# GSM_Signal_Control.net
KiCad netlist of a schematic drawn in Altium Designer
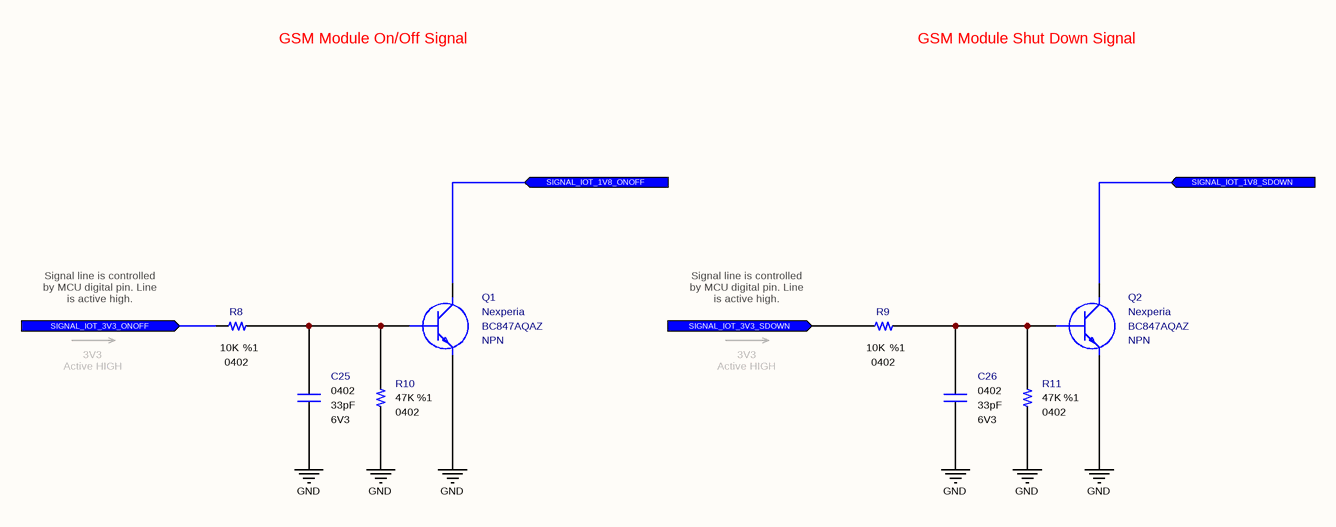
[diagram p0: GSM Signal Control.SchDoc]

(export (version "E")
  (design (tool "Eeschema 10.0.6"))
  (components
    (comp (ref "C25")
      (value "33pF")
      (footprint "CAPACITOR_0402")
      (description "Capacitor - 33pF [0402] (Ceramic)")
      (fields
        (field (name "CASE") "0402")
        (field (name "TOLERANCE") "10%")
        (field (name "VOLTAGE") "6V3")
        (field (name "MANUFACTURER PART NUMBER") "C0402C330J9RACAUTO")
      )
      (libsource (lib "Ovoo_Library") (part "Capacitor - 33pF [0402-6V3]"))
    )
    (comp (ref "C26")
      (value "33pF")
      (footprint "CAPACITOR_0402")
      (description "Capacitor - 33pF [0402] (Ceramic)")
      (fields
        (field (name "CASE") "0402")
        (field (name "TOLERANCE") "10%")
        (field (name "VOLTAGE") "6V3")
        (field (name "MANUFACTURER PART NUMBER") "C0402C330J9RACAUTO")
      )
      (libsource (lib "Ovoo_Library") (part "Capacitor - 33pF [0402-6V3]"))
    )
    (comp (ref "Q1")
      (value "Bipolar NPN Transistors")
      (footprint "SOT1215")
      (description "Bipolar Transistors - BJT BC847AQA/DFN1010D-3/REEL 7\" Q2")
      (fields
        (field (name "MOUSER_PART_NUMBER") "771-BC847AQAZ")
        (field (name "MANUFACTURER_NAME") "Nexperia")
        (field (name "MANUFACTURER_PART_NUMBER") "BC847AQAZ")
        (field (name "POLARITY") "NPN")
      )
      (libsource (lib "Ovoo_Library") (part "Transistor - BC847"))
    )
    (comp (ref "Q2")
      (value "Bipolar NPN Transistors")
      (footprint "SOT1215")
      (description "Bipolar Transistors - BJT BC847AQA/DFN1010D-3/REEL 7\" Q2")
      (fields
        (field (name "MOUSER_PART_NUMBER") "771-BC847AQAZ")
        (field (name "MANUFACTURER_NAME") "Nexperia")
        (field (name "MANUFACTURER_PART_NUMBER") "BC847AQAZ")
        (field (name "POLARITY") "NPN")
      )
      (libsource (lib "Ovoo_Library") (part "Transistor - BC847"))
    )
    (comp (ref "R8")
      (value "10K")
      (footprint "RESISTOR_0402")
      (description "Thick Film Resistors - SMD 1/16 W 10 Kohms 1%")
      (fields
        (field (name "TOLERANCE") "%1")
        (field (name "CASE") "0402")
        (field (name "MANUFACTURER PART NUMBER") "CRCW040210K0FKED")
        (field (name "MOUSER PART NUMBER") "71-CRCW0402-10K-E3")
      )
      (libsource (lib "Ovoo_Library") (part "Resistor - 10K"))
    )
    (comp (ref "R9")
      (value "10K")
      (footprint "RESISTOR_0402")
      (description "Thick Film Resistors - SMD 1/16 W 10 Kohms 1%")
      (fields
        (field (name "TOLERANCE") "%1")
        (field (name "CASE") "0402")
        (field (name "MANUFACTURER PART NUMBER") "CRCW040210K0FKED")
        (field (name "MOUSER PART NUMBER") "71-CRCW0402-10K-E3")
      )
      (libsource (lib "Ovoo_Library") (part "Resistor - 10K"))
    )
    (comp (ref "R10")
      (value "47K")
      (footprint "RESISTOR_0402")
      (description "Thick Film Resistors - SMD 1/16 W 47 Kohms 1%")
      (fields
        (field (name "TOLERANCE") "%1")
        (field (name "CASE") "0402")
        (field (name "MANUFACTURER PART NUMBER") "CRCW040247K0FKED")
        (field (name "MOUSER PART NUMBER") "71-CRCW0402-47K-E3")
      )
      (libsource (lib "Ovoo_Library") (part "Resistor - 47K"))
    )
    (comp (ref "R11")
      (value "47K")
      (footprint "RESISTOR_0402")
      (description "Thick Film Resistors - SMD 1/16 W 47 Kohms 1%")
      (fields
        (field (name "TOLERANCE") "%1")
        (field (name "CASE") "0402")
        (field (name "MANUFACTURER PART NUMBER") "CRCW040247K0FKED")
        (field (name "MOUSER PART NUMBER") "71-CRCW0402-47K-E3")
      )
      (libsource (lib "Ovoo_Library") (part "Resistor - 47K"))
    )
  )
  (nets
    (net (code "1") (name "/SIGNAL_IOT_1V8_ONOFF") (class "Default")
      (node (ref "Q1") (pin "3") (pinfunction "C_3") (pintype "passive"))
    )
    (net (code "2") (name "/SIGNAL_IOT_1V8_SDOWN") (class "Default")
      (node (ref "Q2") (pin "3") (pinfunction "C_3") (pintype "passive"))
    )
    (net (code "3") (name "/SIGNAL_IOT_3V3_ONOFF") (class "Default")
      (node (ref "R8") (pin "2") (pinfunction "2_2") (pintype "passive"))
    )
    (net (code "4") (name "/SIGNAL_IOT_3V3_SDOWN") (class "Default")
      (node (ref "R9") (pin "2") (pinfunction "2_2") (pintype "passive"))
    )
    (net (code "5") (name "GND") (class "Default")
      (node (ref "C25") (pin "2") (pinfunction "2_2") (pintype "passive"))
      (node (ref "C26") (pin "2") (pinfunction "2_2") (pintype "passive"))
      (node (ref "Q1") (pin "2") (pinfunction "E_2") (pintype "passive"))
      (node (ref "Q2") (pin "2") (pinfunction "E_2") (pintype "passive"))
      (node (ref "R10") (pin "1") (pinfunction "1_1") (pintype "passive"))
      (node (ref "R11") (pin "1") (pinfunction "1_1") (pintype "passive"))
    )
    (net (code "6") (name "Net-(Q1-B)") (class "Default")
      (node (ref "C25") (pin "1") (pinfunction "1_1") (pintype "passive"))
      (node (ref "Q1") (pin "1") (pinfunction "B_1") (pintype "passive"))
      (node (ref "R10") (pin "2") (pinfunction "2_2") (pintype "passive"))
      (node (ref "R8") (pin "1") (pinfunction "1_1") (pintype "passive"))
    )
    (net (code "7") (name "Net-(Q2-B)") (class "Default")
      (node (ref "C26") (pin "1") (pinfunction "1_1") (pintype "passive"))
      (node (ref "Q2") (pin "1") (pinfunction "B_1") (pintype "passive"))
      (node (ref "R11") (pin "2") (pinfunction "2_2") (pintype "passive"))
      (node (ref "R9") (pin "1") (pinfunction "1_1") (pintype "passive"))
    )
  )
)
